# txs0108e.net
KiCad netlist of a schematic drawn in EAGLE
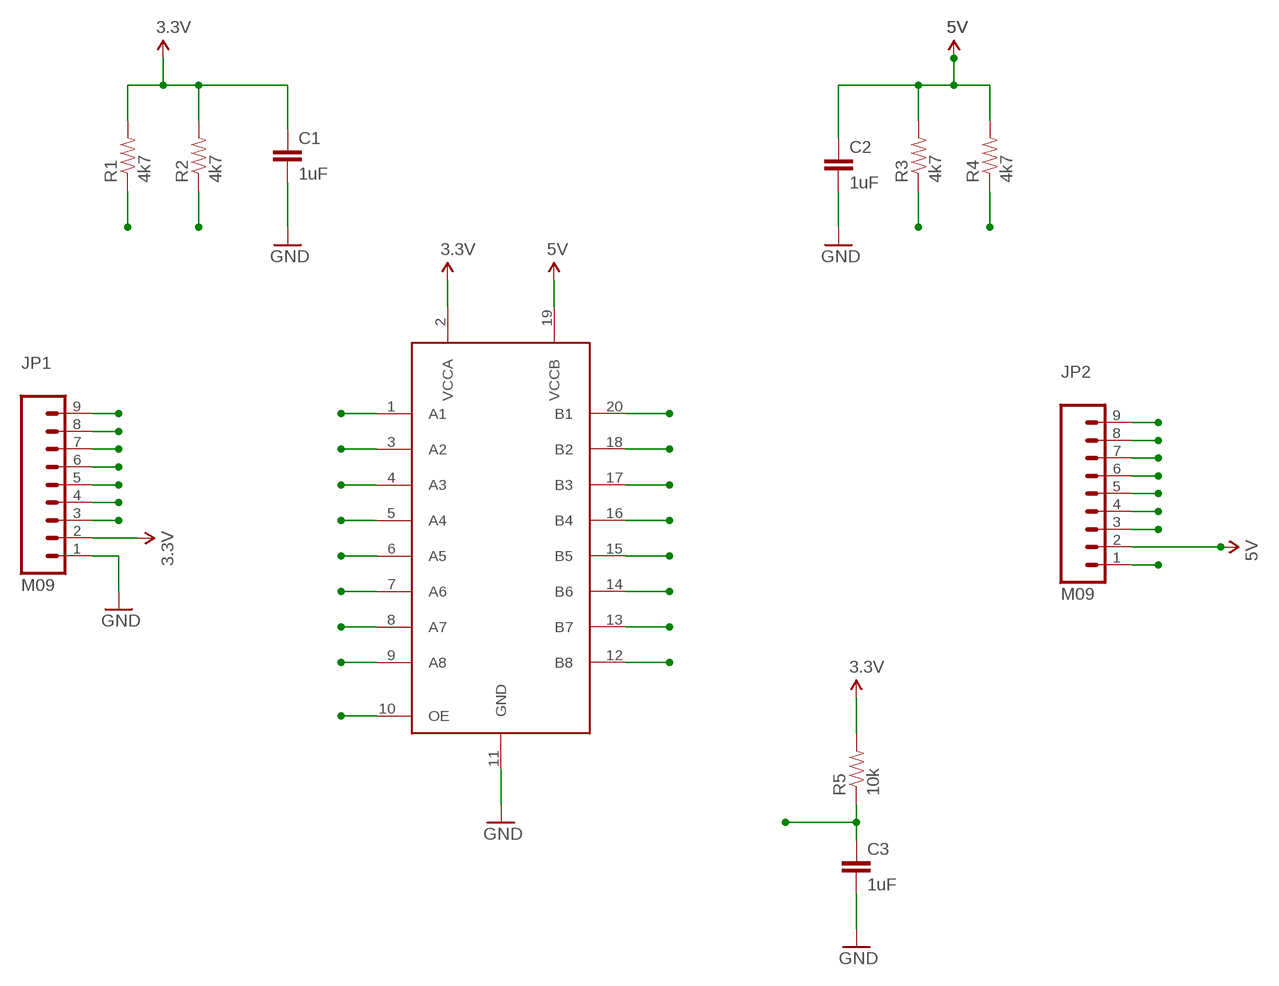
[diagram p0: schematic, sheet 1]

(export (version "E")
  (design (tool "Eeschema 10.0.6"))
  (components
    (comp (ref "C1")
      (value "1uF")
      (footprint "eagle-import:0603-CAP")
      (libsource (lib "eagle-import") (part "CAP0603-CAP"))
    )
    (comp (ref "C2")
      (value "1uF")
      (footprint "eagle-import:0603-CAP")
      (libsource (lib "eagle-import") (part "CAP0603-CAP"))
    )
    (comp (ref "C3")
      (value "1uF")
      (footprint "eagle-import:0603-CAP")
      (libsource (lib "eagle-import") (part "CAP0603-CAP"))
    )
    (comp (ref "JP1")
      (value "M09")
      (footprint "eagle-import:1X09")
      (libsource (lib "eagle-import") (part "M09"))
    )
    (comp (ref "JP2")
      (value "M09")
      (footprint "eagle-import:1X09")
      (libsource (lib "eagle-import") (part "M09"))
    )
    (comp (ref "R1")
      (value "4k7")
      (footprint "eagle-import:0603-RES")
      (libsource (lib "eagle-import") (part "RESISTOR0603-RES"))
    )
    (comp (ref "R2")
      (value "4k7")
      (footprint "eagle-import:0603-RES")
      (libsource (lib "eagle-import") (part "RESISTOR0603-RES"))
    )
    (comp (ref "R3")
      (value "4k7")
      (footprint "eagle-import:0603-RES")
      (libsource (lib "eagle-import") (part "RESISTOR0603-RES"))
    )
    (comp (ref "R4")
      (value "4k7")
      (footprint "eagle-import:0603-RES")
      (libsource (lib "eagle-import") (part "RESISTOR0603-RES"))
    )
    (comp (ref "R5")
      (value "10k")
      (footprint "eagle-import:0603-RES")
      (libsource (lib "eagle-import") (part "RESISTOR0603-RES"))
    )
    (comp (ref "U$1")
      (value "TXS0108E")
      (footprint "eagle-import:TSSOP20")
      (libsource (lib "eagle-import") (part "TXS0108E"))
    )
  )
  (nets
    (net (code "1") (name "/A1") (class "Default")
      (node (ref "JP1") (pin "3") (pinfunction "3_3") (pintype "passive"))
      (node (ref "R1") (pin "1") (pinfunction "1_1") (pintype "passive"))
      (node (ref "U$1") (pin "1") (pinfunction "A1_1") (pintype "bidirectional"))
    )
    (net (code "2") (name "/A2") (class "Default")
      (node (ref "JP1") (pin "4") (pinfunction "4_4") (pintype "passive"))
      (node (ref "R2") (pin "1") (pinfunction "1_1") (pintype "passive"))
      (node (ref "U$1") (pin "3") (pinfunction "A2_3") (pintype "bidirectional"))
    )
    (net (code "3") (name "/A3") (class "Default")
      (node (ref "JP1") (pin "5") (pinfunction "5_5") (pintype "passive"))
      (node (ref "U$1") (pin "4") (pinfunction "A3_4") (pintype "bidirectional"))
    )
    (net (code "4") (name "/A4") (class "Default")
      (node (ref "JP1") (pin "6") (pinfunction "6_6") (pintype "passive"))
      (node (ref "U$1") (pin "5") (pinfunction "A4_5") (pintype "bidirectional"))
    )
    (net (code "5") (name "/A5") (class "Default")
      (node (ref "JP1") (pin "7") (pinfunction "7_7") (pintype "passive"))
      (node (ref "U$1") (pin "6") (pinfunction "A5_6") (pintype "bidirectional"))
    )
    (net (code "6") (name "/A6") (class "Default")
      (node (ref "JP1") (pin "8") (pinfunction "8_8") (pintype "passive"))
      (node (ref "U$1") (pin "7") (pinfunction "A6_7") (pintype "bidirectional"))
    )
    (net (code "7") (name "/A7") (class "Default")
      (node (ref "JP1") (pin "9") (pinfunction "9_9") (pintype "passive"))
      (node (ref "U$1") (pin "8") (pinfunction "A7_8") (pintype "bidirectional"))
    )
    (net (code "8") (name "/B1") (class "Default")
      (node (ref "JP2") (pin "3") (pinfunction "3_3") (pintype "passive"))
      (node (ref "R3") (pin "1") (pinfunction "1_1") (pintype "passive"))
      (node (ref "U$1") (pin "20") (pinfunction "B1_20") (pintype "bidirectional"))
    )
    (net (code "9") (name "/B2") (class "Default")
      (node (ref "JP2") (pin "4") (pinfunction "4_4") (pintype "passive"))
      (node (ref "R4") (pin "1") (pinfunction "1_1") (pintype "passive"))
      (node (ref "U$1") (pin "18") (pinfunction "B2_18") (pintype "bidirectional"))
    )
    (net (code "10") (name "/B3") (class "Default")
      (node (ref "JP2") (pin "5") (pinfunction "5_5") (pintype "passive"))
      (node (ref "U$1") (pin "17") (pinfunction "B3_17") (pintype "bidirectional"))
    )
    (net (code "11") (name "/B4") (class "Default")
      (node (ref "JP2") (pin "6") (pinfunction "6_6") (pintype "passive"))
      (node (ref "U$1") (pin "16") (pinfunction "B4_16") (pintype "bidirectional"))
    )
    (net (code "12") (name "/B5") (class "Default")
      (node (ref "JP2") (pin "7") (pinfunction "7_7") (pintype "passive"))
      (node (ref "U$1") (pin "15") (pinfunction "B5_15") (pintype "bidirectional"))
    )
    (net (code "13") (name "/B6") (class "Default")
      (node (ref "JP2") (pin "8") (pinfunction "8_8") (pintype "passive"))
      (node (ref "U$1") (pin "14") (pinfunction "B6_14") (pintype "bidirectional"))
    )
    (net (code "14") (name "/B7") (class "Default")
      (node (ref "JP2") (pin "9") (pinfunction "9_9") (pintype "passive"))
      (node (ref "U$1") (pin "13") (pinfunction "B7_13") (pintype "bidirectional"))
    )
    (net (code "15") (name "/OE") (class "Default")
      (node (ref "C3") (pin "1") (pinfunction "1_1") (pintype "passive"))
      (node (ref "R5") (pin "1") (pinfunction "1_1") (pintype "passive"))
      (node (ref "U$1") (pin "10") (pinfunction "OE_10") (pintype "bidirectional"))
    )
    (net (code "16") (name "3.3V") (class "Default")
      (node (ref "C1") (pin "1") (pinfunction "1_1") (pintype "passive"))
      (node (ref "JP1") (pin "2") (pinfunction "2_2") (pintype "passive"))
      (node (ref "R1") (pin "2") (pinfunction "2_2") (pintype "passive"))
      (node (ref "R2") (pin "2") (pinfunction "2_2") (pintype "passive"))
      (node (ref "R5") (pin "2") (pinfunction "2_2") (pintype "passive"))
      (node (ref "U$1") (pin "2") (pinfunction "VCCA_2") (pintype "bidirectional"))
    )
    (net (code "17") (name "5V") (class "Default")
      (node (ref "C2") (pin "1") (pinfunction "1_1") (pintype "passive"))
      (node (ref "JP2") (pin "2") (pinfunction "2_2") (pintype "passive"))
      (node (ref "R3") (pin "2") (pinfunction "2_2") (pintype "passive"))
      (node (ref "R4") (pin "2") (pinfunction "2_2") (pintype "passive"))
      (node (ref "U$1") (pin "19") (pinfunction "VCCB_19") (pintype "bidirectional"))
    )
    (net (code "18") (name "GND") (class "Default")
      (node (ref "C1") (pin "2") (pinfunction "2_2") (pintype "passive"))
      (node (ref "C2") (pin "2") (pinfunction "2_2") (pintype "passive"))
      (node (ref "C3") (pin "2") (pinfunction "2_2") (pintype "passive"))
      (node (ref "JP1") (pin "1") (pinfunction "1_1") (pintype "passive"))
      (node (ref "U$1") (pin "11") (pinfunction "GND_11") (pintype "bidirectional"))
    )
    (net (code "19") (name "unconnected-(JP2-Pad1)") (class "Default")
      (node (ref "JP2") (pin "1") (pinfunction "1_1") (pintype "passive"))
    )
    (net (code "20") (name "unconnected-(U$1-A8-Pad9)") (class "Default")
      (node (ref "U$1") (pin "9") (pinfunction "A8_9") (pintype "bidirectional"))
    )
    (net (code "21") (name "unconnected-(U$1-B8-Pad12)") (class "Default")
      (node (ref "U$1") (pin "12") (pinfunction "B8_12") (pintype "bidirectional"))
    )
  )
)
